# RF_VCO.net
KiCad netlist of a schematic drawn in Altium Designer
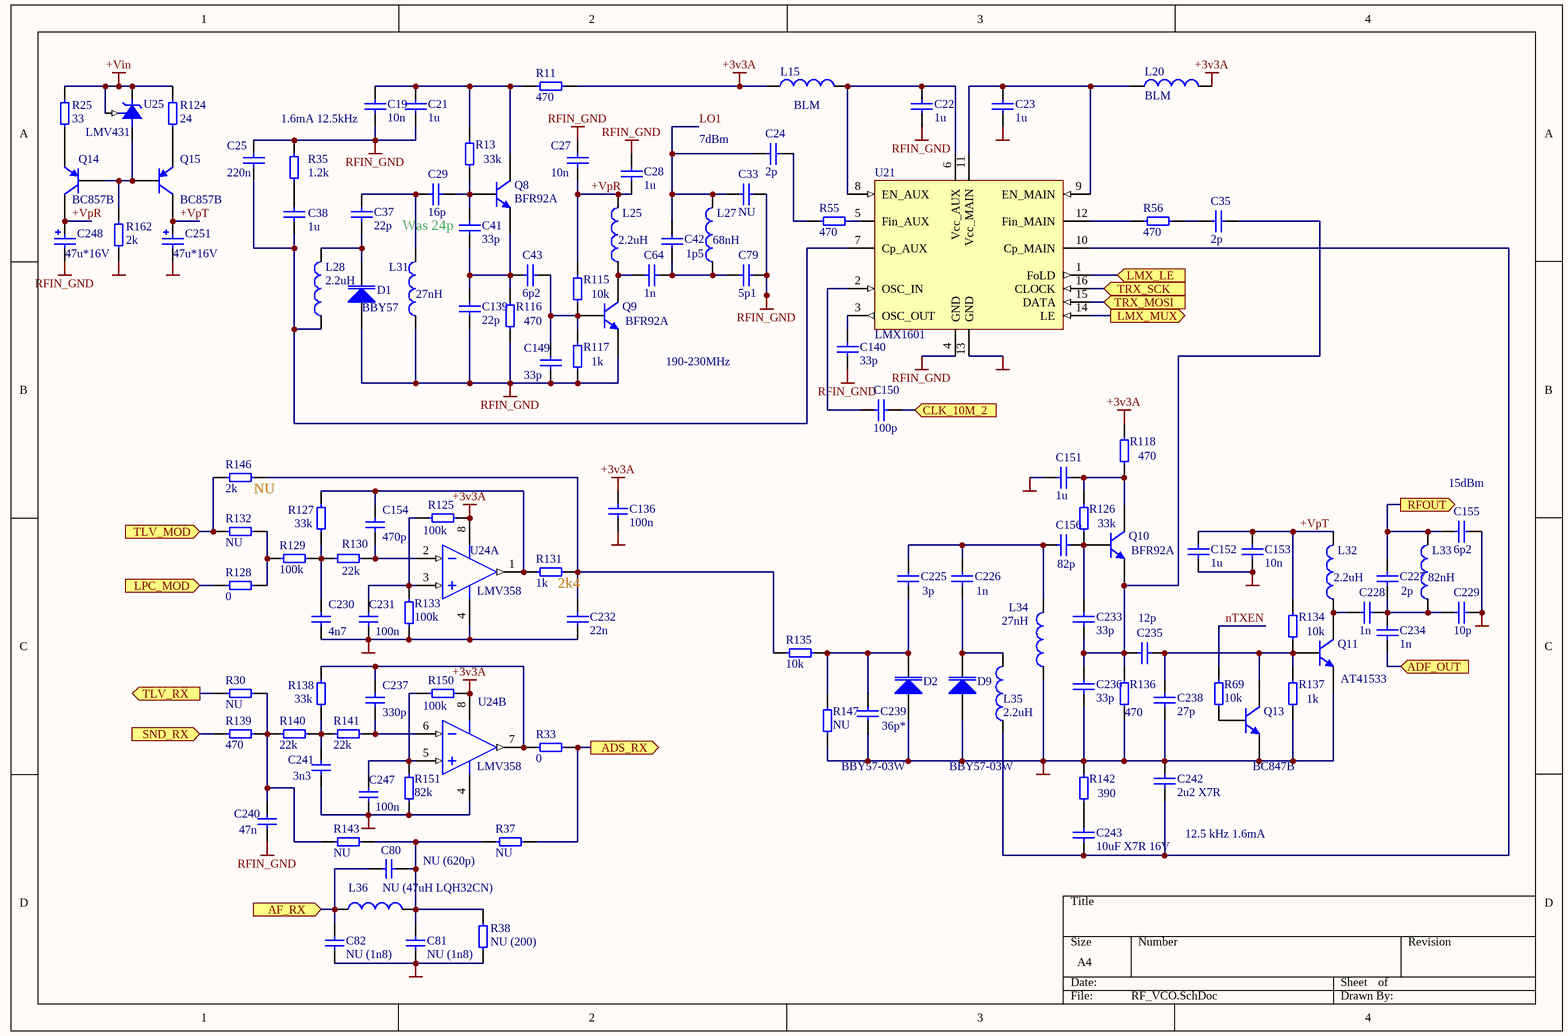
[diagram p0: RF_VCO.SchDoc]

(export (version "E")
  (design (tool "Eeschema 10.0.6"))
  (components
    (comp (ref "C19")
      (value "10n")
      (footprint "CAPC1608L")
      (description "Capacitor")
      (fields (field (name "PUBLISHER") "Altium Limited"))
      (libsource (lib "MyLibrary") (part "Cap"))
    )
    (comp (ref "C21")
      (value "1u")
      (footprint "CAPC2012L")
      (description "Capacitor")
      (fields (field (name "PUBLISHER") "Altium Limited"))
      (libsource (lib "MyLibrary") (part "Cap"))
    )
    (comp (ref "C22")
      (value "1u")
      (footprint "CAPC2012L")
      (description "Capacitor")
      (fields (field (name "PUBLISHER") "Altium Limited"))
      (libsource (lib "Sch components") (part "Cap"))
    )
    (comp (ref "C23")
      (value "1u")
      (footprint "CAPC2012L")
      (description "Capacitor")
      (fields (field (name "PUBLISHER") "Altium Limited"))
      (libsource (lib "Sch components") (part "Cap"))
    )
    (comp (ref "C24")
      (value "2p")
      (footprint "CAPC1608L")
      (description "Capacitor")
      (fields (field (name "PUBLISHER") "Altium Limited"))
      (libsource (lib "Sch components") (part "Cap"))
    )
    (comp (ref "C25")
      (value "220n")
      (footprint "CAPC1608L")
      (description "Capacitor")
      (fields (field (name "PUBLISHER") "Altium Limited"))
      (libsource (lib "MyLibrary") (part "Cap"))
    )
    (comp (ref "C27")
      (value "10n")
      (footprint "CAPC1608L")
      (description "Capacitor")
      (fields (field (name "PUBLISHER") "Altium Limited"))
      (libsource (lib "MyLibrary") (part "Cap"))
    )
    (comp (ref "C28")
      (value "1u")
      (footprint "CAPC2012L")
      (description "Capacitor")
      (fields (field (name "PUBLISHER") "Altium Limited"))
      (libsource (lib "MyLibrary") (part "Cap"))
    )
    (comp (ref "C29")
      (value "16p")
      (footprint "CAPC1608L")
      (description "Capacitor")
      (fields (field (name "PUBLISHER") "Altium Limited"))
      (libsource (lib "MyLibrary") (part "Cap"))
    )
    (comp (ref "C33")
      (value "NU")
      (footprint "CAPC1608L")
      (description "Capacitor")
      (fields (field (name "PUBLISHER") "Altium Limited"))
      (libsource (lib "MyLibrary") (part "Cap"))
    )
    (comp (ref "C35")
      (value "2p")
      (footprint "CAPC1608L")
      (description "Capacitor")
      (fields (field (name "PUBLISHER") "Altium Limited"))
      (libsource (lib "MyLibrary") (part "Cap"))
    )
    (comp (ref "C37")
      (value "22p")
      (footprint "CAPC1608L")
      (description "Capacitor")
      (fields (field (name "PUBLISHER") "Altium Limited"))
      (libsource (lib "MyLibrary") (part "Cap"))
    )
    (comp (ref "C38")
      (value "1u")
      (footprint "CAPC2012L")
      (description "Capacitor")
      (fields (field (name "PUBLISHER") "Altium Limited"))
      (libsource (lib "MyLibrary") (part "Cap"))
    )
    (comp (ref "C41")
      (value "33p")
      (footprint "CAPC1608L")
      (description "Capacitor")
      (fields (field (name "PUBLISHER") "Altium Limited"))
      (libsource (lib "MyLibrary") (part "Cap"))
    )
    (comp (ref "C42")
      (value "1p5")
      (footprint "CAPC1608L")
      (description "Capacitor")
      (fields (field (name "PUBLISHER") "Altium Limited"))
      (libsource (lib "MyLibrary") (part "Cap"))
    )
    (comp (ref "C43")
      (value "6p2")
      (footprint "CAPC1608L")
      (description "Capacitor")
      (fields (field (name "PUBLISHER") "Altium Limited"))
      (libsource (lib "MyLibrary") (part "Cap"))
    )
    (comp (ref "C64")
      (value "1n")
      (footprint "CAPC1608L")
      (description "Capacitor")
      (fields (field (name "PUBLISHER") "Altium Limited"))
      (libsource (lib "MyLibrary") (part "Cap"))
    )
    (comp (ref "C79")
      (value "5p1")
      (footprint "CAPC1608L")
      (description "Capacitor")
      (fields (field (name "PUBLISHER") "Altium Limited"))
      (libsource (lib "MyLibrary") (part "Cap"))
    )
    (comp (ref "C80")
      (value "NU (620p)")
      (footprint "CAPC1608L")
      (description "Capacitor")
      (fields (field (name "PUBLISHER") "Altium Limited"))
      (libsource (lib "") (part "Cap_1"))
    )
    (comp (ref "C81")
      (value "NU (1n8)")
      (footprint "CAPC1608L")
      (description "Capacitor")
      (fields (field (name "PUBLISHER") "Altium Limited"))
      (libsource (lib "") (part "Cap_1"))
    )
    (comp (ref "C82")
      (value "NU (1n8)")
      (footprint "CAPC1608L")
      (description "Capacitor")
      (fields (field (name "PUBLISHER") "Altium Limited"))
      (libsource (lib "") (part "Cap_1"))
    )
    (comp (ref "C136")
      (value "100n")
      (footprint "CAPC1608L")
      (description "Capacitor")
      (fields (field (name "PUBLISHER") "Altium Limited"))
      (libsource (lib "") (part "Cap_1"))
    )
    (comp (ref "C139")
      (value "22p")
      (footprint "CAPC1608L")
      (description "Capacitor")
      (fields (field (name "PUBLISHER") "Altium Limited"))
      (libsource (lib "MyLibrary") (part "Cap"))
    )
    (comp (ref "C140")
      (value "33p")
      (footprint "CAPC1608L")
      (description "Capacitor")
      (fields (field (name "PUBLISHER") "Altium Limited"))
      (libsource (lib "MyLibrary") (part "Cap"))
    )
    (comp (ref "C149")
      (value "33p")
      (footprint "CAPC1608L")
      (description "Capacitor")
      (fields (field (name "PUBLISHER") "Altium Limited"))
      (libsource (lib "MyLibrary") (part "Cap"))
    )
    (comp (ref "C150")
      (value "100p")
      (footprint "CAPC1608L")
      (description "Capacitor")
      (fields (field (name "PUBLISHER") "Altium Limited"))
      (libsource (lib "MyLibrary") (part "Cap"))
    )
    (comp (ref "C151")
      (value "1u")
      (footprint "CAPC2012L")
      (description "Capacitor")
      (fields (field (name "PUBLISHER") "Altium Limited"))
      (libsource (lib "MyLibrary") (part "Cap"))
    )
    (comp (ref "C152")
      (value "1u")
      (footprint "CAPC2012L")
      (description "Capacitor")
      (fields (field (name "PUBLISHER") "Altium Limited"))
      (libsource (lib "MyLibrary") (part "Cap"))
    )
    (comp (ref "C153")
      (value "10n")
      (footprint "CAPC1608L")
      (description "Capacitor")
      (fields (field (name "PUBLISHER") "Altium Limited"))
      (libsource (lib "MyLibrary") (part "Cap"))
    )
    (comp (ref "C154")
      (value "470p")
      (footprint "CAPC1608L")
      (description "Capacitor")
      (fields (field (name "PUBLISHER") "Altium Limited"))
      (libsource (lib "") (part "Cap_1"))
    )
    (comp (ref "C155")
      (value "6p2")
      (footprint "CAPC1608L")
      (description "Capacitor")
      (fields (field (name "PUBLISHER") "Altium Limited"))
      (libsource (lib "MyLibrary") (part "Cap"))
    )
    (comp (ref "C156")
      (value "82p")
      (footprint "CAPC1608L")
      (description "Capacitor")
      (fields (field (name "PUBLISHER") "Altium Limited"))
      (libsource (lib "MyLibrary") (part "Cap"))
    )
    (comp (ref "C225")
      (value "3p")
      (footprint "CAPC1608L")
      (description "Capacitor")
      (fields (field (name "PUBLISHER") "Altium Limited"))
      (libsource (lib "MyLibrary") (part "Cap"))
    )
    (comp (ref "C226")
      (value "1n")
      (footprint "CAPC1608L")
      (description "Capacitor")
      (fields (field (name "PUBLISHER") "Altium Limited"))
      (libsource (lib "MyLibrary") (part "Cap"))
    )
    (comp (ref "C227")
      (value "2p")
      (footprint "CAPC1608L")
      (description "Capacitor")
      (fields (field (name "PUBLISHER") "Altium Limited"))
      (libsource (lib "MyLibrary") (part "Cap"))
    )
    (comp (ref "C228")
      (value "1n")
      (footprint "CAPC1608L")
      (description "Capacitor")
      (fields (field (name "PUBLISHER") "Altium Limited"))
      (libsource (lib "MyLibrary") (part "Cap"))
    )
    (comp (ref "C229")
      (value "10p")
      (footprint "CAPC1608L")
      (description "Capacitor")
      (fields (field (name "PUBLISHER") "Altium Limited"))
      (libsource (lib "MyLibrary") (part "Cap"))
    )
    (comp (ref "C230")
      (value "4n7")
      (footprint "CAPC1608L")
      (description "Capacitor")
      (fields (field (name "PUBLISHER") "Altium Limited"))
      (libsource (lib "") (part "Cap_1"))
    )
    (comp (ref "C231")
      (value "100n")
      (footprint "CAPC1608L")
      (description "Capacitor")
      (fields (field (name "PUBLISHER") "Altium Limited"))
      (libsource (lib "") (part "Cap_1"))
    )
    (comp (ref "C232")
      (value "22n")
      (footprint "CAPC1608L")
      (description "Capacitor")
      (fields (field (name "PUBLISHER") "Altium Limited"))
      (libsource (lib "Sch components") (part "Cap"))
    )
    (comp (ref "C233")
      (value "33p")
      (footprint "CAPC1608L")
      (description "Capacitor")
      (fields (field (name "PUBLISHER") "Altium Limited"))
      (libsource (lib "MyLibrary") (part "Cap"))
    )
    (comp (ref "C234")
      (value "1n")
      (footprint "CAPC1608L")
      (description "Capacitor")
      (fields (field (name "PUBLISHER") "Altium Limited"))
      (libsource (lib "MyLibrary") (part "Cap"))
    )
    (comp (ref "C235")
      (value "12p")
      (footprint "CAPC1608L")
      (description "Capacitor")
      (fields (field (name "PUBLISHER") "Altium Limited"))
      (libsource (lib "MyLibrary") (part "Cap"))
    )
    (comp (ref "C236")
      (value "33p")
      (footprint "CAPC1608L")
      (description "Capacitor")
      (fields (field (name "PUBLISHER") "Altium Limited"))
      (libsource (lib "MyLibrary") (part "Cap"))
    )
    (comp (ref "C237")
      (value "330p")
      (footprint "CAPC1608L")
      (description "Capacitor")
      (fields (field (name "PUBLISHER") "Altium Limited"))
      (libsource (lib "") (part "Cap_1"))
    )
    (comp (ref "C238")
      (value "27p")
      (footprint "CAPC1608L")
      (description "Capacitor")
      (fields (field (name "PUBLISHER") "Altium Limited"))
      (libsource (lib "MyLibrary") (part "Cap"))
    )
    (comp (ref "C239")
      (value "36p*")
      (footprint "CAPC1608L")
      (description "Capacitor")
      (fields (field (name "PUBLISHER") "Altium Limited"))
      (libsource (lib "MyLibrary") (part "Cap"))
    )
    (comp (ref "C240")
      (value "47n")
      (footprint "CAPC1608L")
      (description "Capacitor")
      (fields (field (name "PUBLISHER") "Altium Limited"))
      (libsource (lib "") (part "Cap_1"))
    )
    (comp (ref "C241")
      (value "3n3")
      (footprint "CAPC1608L")
      (description "Capacitor")
      (fields (field (name "PUBLISHER") "Altium Limited"))
      (libsource (lib "") (part "Cap_1"))
    )
    (comp (ref "C242")
      (value "2u2 X7R")
      (footprint "CAPC2012L")
      (description "Capacitor")
      (fields (field (name "PUBLISHER") "Altium Limited"))
      (libsource (lib "MyLibrary") (part "Cap"))
    )
    (comp (ref "C243")
      (value "10uF X7R 16V")
      (footprint "CAPC3216M")
      (description "Capacitor")
      (fields (field (name "PUBLISHER") "Altium Limited"))
      (libsource (lib "Sch components") (part "Cap"))
    )
    (comp (ref "C247")
      (value "100n")
      (footprint "CAPC1608L")
      (description "Capacitor")
      (fields (field (name "PUBLISHER") "Altium Limited"))
      (libsource (lib "") (part "Cap_1"))
    )
    (comp (ref "C248")
      (value "47u*16V")
      (footprint "Case_C")
      (description "Polarized Capacitor (Surface Mount)")
      (fields (field (name "PUBLISHER") "Altium Limited"))
      (libsource (lib "Sch components") (part "Cap Pol"))
    )
    (comp (ref "C251")
      (value "47u*16V")
      (footprint "Case_C")
      (description "Polarized Capacitor (Surface Mount)")
      (fields (field (name "PUBLISHER") "Altium Limited"))
      (libsource (lib "Sch components") (part "Cap Pol"))
    )
    (comp (ref "D1")
      (value "BBY57")
      (footprint "SOD-323")
      (description "Silicon High Q Hyperabrupt Tuning Diode")
      (fields (field (name "PUBLISHER") "Altium Limited"))
      (libsource (lib "Infineon Discrete Diode") (part "BBY57-03W"))
    )
    (comp (ref "D2")
      (value "BBY57-03W")
      (footprint "SOD-323")
      (description "Silicon High Q Hyperabrupt Tuning Diode")
      (fields (field (name "PUBLISHER") "Altium Limited"))
      (libsource (lib "Infineon Discrete Diode") (part "BBY57-03W"))
    )
    (comp (ref "D9")
      (value "BBY57-03W")
      (footprint "SOD-323")
      (description "Silicon High Q Hyperabrupt Tuning Diode")
      (fields (field (name "PUBLISHER") "Altium Limited"))
      (libsource (lib "Infineon Discrete Diode") (part "BBY57-03W"))
    )
    (comp (ref "L15")
      (value "BLM")
      (footprint "CAPC2012N")
      (description "Ferrite Bead")
      (fields (field (name "PUBLISHER") "Altium Limited"))
      (libsource (lib "Sch components") (part "Ferrite Bead"))
    )
    (comp (ref "L20")
      (value "BLM")
      (footprint "CAPC2012N")
      (description "Ferrite Bead")
      (fields (field (name "PUBLISHER") "Altium Limited"))
      (libsource (lib "") (part "Ferrite Bead_1"))
    )
    (comp (ref "L25") (value "2.2uH") (footprint "INDC2012L") (libsource (lib "MyLibrary") (part "INDUCTOR")))
    (comp (ref "L27") (value "68nH") (footprint "INDC2012L") (libsource (lib "MyLibrary") (part "INDUCTOR")))
    (comp (ref "L28") (value "2.2uH") (footprint "INDC2012L") (libsource (lib "MyLibrary") (part "INDUCTOR")))
    (comp (ref "L31") (value "27nH") (footprint "INDC2012L") (libsource (lib "MyLibrary") (part "INDUCTOR")))
    (comp (ref "L32") (value "2.2uH") (footprint "INDC2012L") (libsource (lib "MyLibrary") (part "INDUCTOR")))
    (comp (ref "L33") (value "82nH") (footprint "INDC2012L") (libsource (lib "MyLibrary") (part "INDUCTOR")))
    (comp (ref "L34") (value "27nH") (footprint "INDC2012L") (libsource (lib "MyLibrary") (part "INDUCTOR")))
    (comp (ref "L35") (value "2.2uH") (footprint "INDC2012L") (libsource (lib "MyLibrary") (part "INDUCTOR")))
    (comp (ref "L36")
      (value "NU (47uH LQH32CN)")
      (footprint "CAPC3225N")
      (libsource (lib "MyLibrary") (part "INDUCTOR"))
    )
    (comp (ref "Q8")
      (value "BFR92A")
      (footprint "SOT-23")
      (description "NPN 5 GHz Wideband Transistor")
      (fields (field (name "PUBLISHER") "Altium Limited"))
      (libsource (lib "Philips Discrete BJT - RF Transistor") (part "BFR92A"))
    )
    (comp (ref "Q9")
      (value "BFR92A")
      (footprint "SOT-23")
      (description "NPN 5 GHz Wideband Transistor")
      (fields (field (name "PUBLISHER") "Altium Limited"))
      (libsource (lib "Philips Discrete BJT - RF Transistor") (part "BFR92A"))
    )
    (comp (ref "Q10")
      (value "BFR92A")
      (footprint "SOT-23")
      (description "NPN 5 GHz Wideband Transistor")
      (fields (field (name "PUBLISHER") "Altium Limited"))
      (libsource (lib "Philips Discrete BJT - RF Transistor") (part "BFR92A"))
    )
    (comp (ref "Q11")
      (value "AT41533")
      (footprint "SOT-23")
      (description "NPN 5 GHz Wideband Transistor")
      (fields (field (name "PUBLISHER") "Altium Limited"))
      (libsource (lib "Philips Discrete BJT - RF Transistor") (part "BFR92A"))
    )
    (comp (ref "Q13")
      (value "BC847B")
      (footprint "SOT23_N")
      (description "NPN General-purpose Transistor")
      (fields (field (name "PUBLISHER") "Altium Limited"))
      (libsource (lib "Philips Discrete BJT - Low Power") (part "BC847B"))
    )
    (comp (ref "Q14")
      (value "BC857B")
      (footprint "SOT23_N")
      (description "PNP General-purpose Transistor")
      (fields (field (name "PUBLISHER") "Altium Limited"))
      (libsource (lib "Philips Discrete BJT - Low Power") (part "BC857B"))
    )
    (comp (ref "Q15")
      (value "BC857B")
      (footprint "SOT23_N")
      (description "PNP General-purpose Transistor")
      (fields (field (name "PUBLISHER") "Altium Limited"))
      (libsource (lib "Philips Discrete BJT - Low Power") (part "BC857B"))
    )
    (comp (ref "R11")
      (value "470")
      (footprint "RESC1608L")
      (description "Resistor")
      (fields (field (name "PUBLISHER") "Altium Limited"))
      (libsource (lib "Sch components") (part "Res"))
    )
    (comp (ref "R13")
      (value "33k")
      (footprint "RESC1608L")
      (description "Resistor")
      (fields (field (name "PUBLISHER") "Altium Limited"))
      (libsource (lib "Sch components") (part "Res"))
    )
    (comp (ref "R25")
      (value "33")
      (footprint "RESC1608L")
      (description "Resistor")
      (fields (field (name "PUBLISHER") "Altium Limited"))
      (libsource (lib "Sch components") (part "Res"))
    )
    (comp (ref "R30")
      (value "NU")
      (footprint "RESC1608L")
      (description "Resistor")
      (fields (field (name "PUBLISHER") "Altium Limited"))
      (libsource (lib "Sch components") (part "Res"))
    )
    (comp (ref "R33")
      (value "0")
      (footprint "RESC1608L")
      (description "Resistor")
      (fields (field (name "PUBLISHER") "Altium Limited"))
      (libsource (lib "Sch components") (part "Res"))
    )
    (comp (ref "R35")
      (value "1.2k")
      (footprint "RESC1608L")
      (description "Resistor")
      (fields (field (name "PUBLISHER") "Altium Limited"))
      (libsource (lib "Sch components") (part "Res"))
    )
    (comp (ref "R37")
      (value "NU")
      (footprint "RESC1608L")
      (description "Resistor")
      (fields (field (name "PUBLISHER") "Altium Limited"))
      (libsource (lib "") (part "Res_1"))
    )
    (comp (ref "R38")
      (value "NU (200)")
      (footprint "RESC1608L")
      (description "Resistor")
      (fields (field (name "PUBLISHER") "Altium Limited"))
      (libsource (lib "Sch components") (part "Res"))
    )
    (comp (ref "R55")
      (value "470")
      (footprint "RESC1608L")
      (description "Resistor")
      (fields (field (name "PUBLISHER") "Altium Limited"))
      (libsource (lib "Sch components") (part "Res"))
    )
    (comp (ref "R56")
      (value "470")
      (footprint "RESC1608L")
      (description "Resistor")
      (fields (field (name "PUBLISHER") "Altium Limited"))
      (libsource (lib "Sch components") (part "Res"))
    )
    (comp (ref "R69")
      (value "10k")
      (footprint "RESC1608L")
      (description "Resistor")
      (fields (field (name "PUBLISHER") "Altium Limited"))
      (libsource (lib "Sch components") (part "Res"))
    )
    (comp (ref "R115")
      (value "10k")
      (footprint "RESC1608L")
      (description "Resistor")
      (fields (field (name "PUBLISHER") "Altium Limited"))
      (libsource (lib "Sch components") (part "Res"))
    )
    (comp (ref "R116")
      (value "470")
      (footprint "RESC1608L")
      (description "Resistor")
      (fields (field (name "PUBLISHER") "Altium Limited"))
      (libsource (lib "Sch components") (part "Res"))
    )
    (comp (ref "R117")
      (value "1k")
      (footprint "RESC1608L")
      (description "Resistor")
      (fields (field (name "PUBLISHER") "Altium Limited"))
      (libsource (lib "Sch components") (part "Res"))
    )
    (comp (ref "R118")
      (value "470")
      (footprint "RESC1608L")
      (description "Resistor")
      (fields (field (name "PUBLISHER") "Altium Limited"))
      (libsource (lib "Sch components") (part "Res"))
    )
    (comp (ref "R124")
      (value "24")
      (footprint "RESC1608L")
      (description "Resistor")
      (fields (field (name "PUBLISHER") "Altium Limited"))
      (libsource (lib "Sch components") (part "Res"))
    )
    (comp (ref "R125")
      (value "100k")
      (footprint "RESC1608L")
      (description "Resistor")
      (fields (field (name "PUBLISHER") "Altium Limited"))
      (libsource (lib "Sch components") (part "Res"))
    )
    (comp (ref "R126")
      (value "33k")
      (footprint "RESC1608L")
      (description "Resistor")
      (fields (field (name "PUBLISHER") "Altium Limited"))
      (libsource (lib "Sch components") (part "Res"))
    )
    (comp (ref "R127")
      (value "33k")
      (footprint "RESC1608L")
      (description "Resistor")
      (fields (field (name "PUBLISHER") "Altium Limited"))
      (libsource (lib "Sch components") (part "Res"))
    )
    (comp (ref "R128")
      (value "0")
      (footprint "RESC1608L")
      (description "Resistor")
      (fields (field (name "PUBLISHER") "Altium Limited"))
      (libsource (lib "Sch components") (part "Res"))
    )
    (comp (ref "R129")
      (value "100k")
      (footprint "RESC1608L")
      (description "Resistor")
      (fields (field (name "PUBLISHER") "Altium Limited"))
      (libsource (lib "Sch components") (part "Res"))
    )
    (comp (ref "R130")
      (value "22k")
      (footprint "RESC1608L")
      (description "Resistor")
      (fields (field (name "PUBLISHER") "Altium Limited"))
      (libsource (lib "Sch components") (part "Res"))
    )
    (comp (ref "R131")
      (value "1k")
      (footprint "RESC1608L")
      (description "Resistor")
      (fields (field (name "PUBLISHER") "Altium Limited"))
      (libsource (lib "Sch components") (part "Res"))
    )
    (comp (ref "R132")
      (value "NU")
      (footprint "RESC1608L")
      (description "Resistor")
      (fields (field (name "PUBLISHER") "Altium Limited"))
      (libsource (lib "Sch components") (part "Res"))
    )
    (comp (ref "R133")
      (value "100k")
      (footprint "RESC1608L")
      (description "Resistor")
      (fields (field (name "PUBLISHER") "Altium Limited"))
      (libsource (lib "Sch components") (part "Res"))
    )
    (comp (ref "R134")
      (value "10k")
      (footprint "RESC1608L")
      (description "Resistor")
      (fields (field (name "PUBLISHER") "Altium Limited"))
      (libsource (lib "Sch components") (part "Res"))
    )
    (comp (ref "R135")
      (value "10k")
      (footprint "RESC1608L")
      (description "Resistor")
      (fields (field (name "PUBLISHER") "Altium Limited"))
      (libsource (lib "Sch components") (part "Res"))
    )
    (comp (ref "R136")
      (value "470")
      (footprint "RESC1608L")
      (description "Resistor")
      (fields (field (name "PUBLISHER") "Altium Limited"))
      (libsource (lib "Sch components") (part "Res"))
    )
    (comp (ref "R137")
      (value "1k")
      (footprint "RESC1608L")
      (description "Resistor")
      (fields (field (name "PUBLISHER") "Altium Limited"))
      (libsource (lib "Sch components") (part "Res"))
    )
    (comp (ref "R138")
      (value "33k")
      (footprint "RESC1608L")
      (description "Resistor")
      (fields (field (name "PUBLISHER") "Altium Limited"))
      (libsource (lib "Sch components") (part "Res"))
    )
    (comp (ref "R139")
      (value "470")
      (footprint "RESC1608L")
      (description "Resistor")
      (fields (field (name "PUBLISHER") "Altium Limited"))
      (libsource (lib "Sch components") (part "Res"))
    )
    (comp (ref "R140")
      (value "22k")
      (footprint "RESC1608L")
      (description "Resistor")
      (fields (field (name "PUBLISHER") "Altium Limited"))
      (libsource (lib "Sch components") (part "Res"))
    )
    (comp (ref "R141")
      (value "22k")
      (footprint "RESC1608L")
      (description "Resistor")
      (fields (field (name "PUBLISHER") "Altium Limited"))
      (libsource (lib "Sch components") (part "Res"))
    )
    (comp (ref "R142")
      (value "390")
      (footprint "RESC1608L")
      (description "Resistor")
      (fields (field (name "PUBLISHER") "Altium Limited"))
      (libsource (lib "Sch components") (part "Res"))
    )
    (comp (ref "R143")
      (value "NU")
      (footprint "RESC1608L")
      (description "Resistor")
      (fields (field (name "PUBLISHER") "Altium Limited"))
      (libsource (lib "") (part "Res_1"))
    )
    (comp (ref "R146")
      (value "2k")
      (footprint "RESC1608L")
      (description "Resistor")
      (fields (field (name "PUBLISHER") "Altium Limited"))
      (libsource (lib "Sch components") (part "Res"))
    )
    (comp (ref "R147")
      (value "NU")
      (footprint "RESC1608L")
      (description "Resistor")
      (fields (field (name "PUBLISHER") "Altium Limited"))
      (libsource (lib "Sch components") (part "Res"))
    )
    (comp (ref "R150")
      (value "100k")
      (footprint "RESC1608L")
      (description "Resistor")
      (fields (field (name "PUBLISHER") "Altium Limited"))
      (libsource (lib "Sch components") (part "Res"))
    )
    (comp (ref "R151")
      (value "82k")
      (footprint "RESC1608L")
      (description "Resistor")
      (fields (field (name "PUBLISHER") "Altium Limited"))
      (libsource (lib "Sch components") (part "Res"))
    )
    (comp (ref "R162")
      (value "2k")
      (footprint "RESC1608L")
      (description "Resistor")
      (fields (field (name "PUBLISHER") "Altium Limited"))
      (libsource (lib "Sch components") (part "Res"))
    )
    (comp (ref "U21")
      (value "LMX1601")
      (footprint "TSSOP65P640X120-16N")
      (description "Synthesizer")
      (libsource (lib "Sch components") (part "LMX1601"))
    )
    (comp (ref "U24")
      (value "LMV358")
      (footprint "SOIC-150-8")
      (description "General Purpose, Low Voltage, Rail-to-Rail Output Operational Amplifiers")
      (fields
        (field (name "PARTNUMBER") "LMV358M")
        (field (name "MANUFACTURER") "National Semiconductor")
        (field (name "PUBLISHER") "Altium Limited")
      )
      (libsource (lib "*") (part "LMV358M"))
    )
    (comp (ref "U25")
      (value "LMV431")
      (footprint "MF03A_N")
      (description "Low-Voltage (1.24V) Adjustable Precision Shunt Regulator")
      (fields
        (field (name "PARTNUMBER") "LMV431AIMF")
        (field (name "MANUFACTURER") "National Semiconductor")
        (field (name "PUBLISHER") "Altium Limited")
      )
      (libsource (lib "NSC MiscPower") (part "LMV431AIMF"))
    )
  )
  (nets
    (net (code "1") (name "+3v3A") (class "Default")
      (node (ref "C136") (pin "1") (pinfunction "1_1") (pintype "passive"))
      (node (ref "L15") (pin "2") (pinfunction "2_2") (pintype "passive"))
      (node (ref "L20") (pin "2") (pinfunction "2_2") (pintype "passive"))
      (node (ref "R11") (pin "2") (pinfunction "2_2") (pintype "passive"))
      (node (ref "R118") (pin "1") (pinfunction "1_1") (pintype "passive"))
      (node (ref "R125") (pin "2") (pinfunction "2_2") (pintype "passive"))
      (node (ref "R150") (pin "2") (pinfunction "2_2") (pintype "passive"))
      (node (ref "U24") (pin "8") (pinfunction "V+_8") (pintype "power_in"))
    )
    (net (code "2") (name "+Vin") (class "Default")
      (node (ref "R124") (pin "2") (pinfunction "2_2") (pintype "passive"))
      (node (ref "R25") (pin "2") (pinfunction "2_2") (pintype "passive"))
      (node (ref "U25") (pin "1") (pinfunction "REF_1") (pintype "input"))
      (node (ref "U25") (pin "2") (pinfunction "K_2") (pintype "passive"))
    )
    (net (code "3") (name "/+VpR") (class "Default")
      (node (ref "C248") (pin "1") (pinfunction "1_1") (pintype "passive"))
      (node (ref "C27") (pin "2") (pinfunction "2_2") (pintype "passive"))
      (node (ref "C28") (pin "2") (pinfunction "2_2") (pintype "passive"))
      (node (ref "L25") (pin "2") (pinfunction "2_2") (pintype "passive"))
      (node (ref "Q14") (pin "3") (pinfunction "C_3") (pintype "passive"))
      (node (ref "R115") (pin "1") (pinfunction "1_1") (pintype "passive"))
    )
    (net (code "4") (name "/+VpT") (class "Default")
      (node (ref "C152") (pin "2") (pinfunction "2_2") (pintype "passive"))
      (node (ref "C153") (pin "2") (pinfunction "2_2") (pintype "passive"))
      (node (ref "C251") (pin "1") (pinfunction "1_1") (pintype "passive"))
      (node (ref "L32") (pin "2") (pinfunction "2_2") (pintype "passive"))
      (node (ref "Q15") (pin "3") (pinfunction "C_3") (pintype "passive"))
      (node (ref "R134") (pin "1") (pinfunction "1_1") (pintype "passive"))
    )
    (net (code "5") (name "/ADF_OUT") (class "Default")
      (node (ref "C234") (pin "2") (pinfunction "2_2") (pintype "passive"))
    )
    (net (code "6") (name "/ADS_RX") (class "Default")
      (node (ref "R33") (pin "2") (pinfunction "2_2") (pintype "passive"))
      (node (ref "R37") (pin "1") (pinfunction "1_1") (pintype "passive"))
    )
    (net (code "7") (name "/AF_RX") (class "Default")
      (node (ref "C80") (pin "2") (pinfunction "2_2") (pintype "passive"))
      (node (ref "C82") (pin "2") (pinfunction "2_2") (pintype "passive"))
      (node (ref "L36") (pin "1") (pinfunction "1_1") (pintype "passive"))
    )
    (net (code "8") (name "/CLK_10M_2") (class "Default")
      (node (ref "C150") (pin "2") (pinfunction "2_2") (pintype "passive"))
    )
    (net (code "9") (name "/LMX_LE") (class "Default")
      (node (ref "U21") (pin "1") (pinfunction "FoLD_1") (pintype "output"))
    )
    (net (code "10") (name "/LMX_MUX") (class "Default")
      (node (ref "U21") (pin "14") (pinfunction "LE_14") (pintype "input"))
    )
    (net (code "11") (name "/LO1") (class "Default")
      (node (ref "C24") (pin "1") (pinfunction "1_1") (pintype "passive"))
      (node (ref "C33") (pin "1") (pinfunction "1_1") (pintype "passive"))
      (node (ref "C42") (pin "2") (pinfunction "2_2") (pintype "passive"))
      (node (ref "L27") (pin "2") (pinfunction "2_2") (pintype "passive"))
    )
    (net (code "12") (name "/LPC_MOD") (class "Default")
      (node (ref "R128") (pin "1") (pinfunction "1_1") (pintype "passive"))
    )
    (net (code "13") (name "/RFOUT") (class "Default")
      (node (ref "C155") (pin "1") (pinfunction "1_1") (pintype "passive"))
      (node (ref "C227") (pin "2") (pinfunction "2_2") (pintype "passive"))
      (node (ref "L33") (pin "2") (pinfunction "2_2") (pintype "passive"))
    )
    (net (code "14") (name "/SND_RX") (class "Default")
      (node (ref "R139") (pin "2") (pinfunction "2_2") (pintype "passive"))
    )
    (net (code "15") (name "/TLV_MOD") (class "Default")
      (node (ref "R132") (pin "1") (pinfunction "1_1") (pintype "passive"))
      (node (ref "R146") (pin "1") (pinfunction "1_1") (pintype "passive"))
    )
    (net (code "16") (name "/TLV_RX") (class "Default")
      (node (ref "R30") (pin "2") (pinfunction "2_2") (pintype "passive"))
    )
    (net (code "17") (name "/TRX_MOSI") (class "Default")
      (node (ref "U21") (pin "15") (pinfunction "DATA_15") (pintype "input"))
    )
    (net (code "18") (name "/TRX_SCK") (class "Default")
      (node (ref "U21") (pin "16") (pinfunction "CLOCK_16") (pintype "input"))
    )
    (net (code "19") (name "/nTXEN") (class "Default")
      (node (ref "R69") (pin "1") (pinfunction "1_1") (pintype "passive"))
    )
    (net (code "20") (name "GND") (class "Default")
      (node (ref "C136") (pin "2") (pinfunction "2_2") (pintype "passive"))
      (node (ref "C151") (pin "2") (pinfunction "2_2") (pintype "passive"))
      (node (ref "C152") (pin "1") (pinfunction "1_1") (pintype "passive"))
      (node (ref "C153") (pin "1") (pinfunction "1_1") (pintype "passive"))
      (node (ref "C155") (pin "2") (pinfunction "2_2") (pintype "passive"))
      (node (ref "C229") (pin "2") (pinfunction "2_2") (pintype "passive"))
      (node (ref "C23") (pin "1") (pinfunction "1_1") (pintype "passive"))
      (node (ref "C230") (pin "2") (pinfunction "2_2") (pintype "passive"))
      (node (ref "C231") (pin "2") (pinfunction "2_2") (pintype "passive"))
      (node (ref "C232") (pin "2") (pinfunction "2_2") (pintype "passive"))
      (node (ref "C236") (pin "2") (pinfunction "2_2") (pintype "passive"))
      (node (ref "C238") (pin "2") (pinfunction "2_2") (pintype "passive"))
      (node (ref "C239") (pin "1") (pinfunction "1_1") (pintype "passive"))
      (node (ref "C241") (pin "2") (pinfunction "2_2") (pintype "passive"))
      (node (ref "C242") (pin "1") (pinfunction "1_1") (pintype "passive"))
      (node (ref "C247") (pin "2") (pinfunction "2_2") (pintype "passive"))
      (node (ref "C251") (pin "2") (pinfunction "2_2") (pintype "passive"))
      (node (ref "C81") (pin "1") (pinfunction "1_1") (pintype "passive"))
      (node (ref "C82") (pin "1") (pinfunction "1_1") (pintype "passive"))
      (node (ref "D2") (pin "2") (pinfunction "A_2") (pintype "passive"))
      (node (ref "D9") (pin "2") (pinfunction "A_2") (pintype "passive"))
      (node (ref "L34") (pin "1") (pinfunction "1_1") (pintype "passive"))
      (node (ref "Q11") (pin "2") (pinfunction "E_2") (pintype "passive"))
      (node (ref "Q13") (pin "2") (pinfunction "E_2") (pintype "passive"))
      (node (ref "R133") (pin "2") (pinfunction "2_2") (pintype "passive"))
      (node (ref "R136") (pin "2") (pinfunction "2_2") (pintype "passive"))
      (node (ref "R137") (pin "2") (pinfunction "2_2") (pintype "passive"))
      (node (ref "R142") (pin "1") (pinfunction "1_1") (pintype "passive"))
      (node (ref "R147") (pin "1") (pinfunction "1_1") (pintype "passive"))
      (node (ref "R151") (pin "2") (pinfunction "2_2") (pintype "passive"))
      (node (ref "R162") (pin "1") (pinfunction "1_1") (pintype "passive"))
      (node (ref "R38") (pin "2") (pinfunction "2_2") (pintype "passive"))
      (node (ref "U21") (pin "13") (pinfunction "GND_13") (pintype "power_in"))
      (node (ref "U24") (pin "4") (pinfunction "V-_4") (pintype "power_in"))
    )
    (net (code "21") (name "Net-(C24-Pad2)") (class "Default")
      (node (ref "C24") (pin "2") (pinfunction "2_2") (pintype "passive"))
      (node (ref "R55") (pin "1") (pinfunction "1_1") (pintype "passive"))
    )
    (net (code "22") (name "Net-(C29-Pad2)") (class "Default")
      (node (ref "C29") (pin "2") (pinfunction "2_2") (pintype "passive"))
      (node (ref "C37") (pin "2") (pinfunction "2_2") (pintype "passive"))
      (node (ref "L31") (pin "2") (pinfunction "2_2") (pintype "passive"))
    )
    (net (code "23") (name "Net-(C35-Pad1)") (class "Default")
      (node (ref "C35") (pin "1") (pinfunction "1_1") (pintype "passive"))
      (node (ref "R56") (pin "2") (pinfunction "2_2") (pintype "passive"))
    )
    (net (code "24") (name "Net-(C38-Pad1)") (class "Default")
      (node (ref "C38") (pin "1") (pinfunction "1_1") (pintype "passive"))
      (node (ref "R35") (pin "2") (pinfunction "2_2") (pintype "passive"))
    )
    (net (code "25") (name "Net-(C42-Pad1)") (class "Default")
      (node (ref "C42") (pin "1") (pinfunction "1_1") (pintype "passive"))
      (node (ref "C64") (pin "1") (pinfunction "1_1") (pintype "passive"))
      (node (ref "C79") (pin "1") (pinfunction "1_1") (pintype "passive"))
      (node (ref "L27") (pin "1") (pinfunction "1_1") (pintype "passive"))
    )
    (net (code "26") (name "Net-(C80-Pad1)") (class "Default")
      (node (ref "C80") (pin "1") (pinfunction "1_1") (pintype "passive"))
      (node (ref "C81") (pin "2") (pinfunction "2_2") (pintype "passive"))
      (node (ref "L36") (pin "2") (pinfunction "2_2") (pintype "passive"))
      (node (ref "R143") (pin "2") (pinfunction "2_2") (pintype "passive"))
      (node (ref "R37") (pin "2") (pinfunction "2_2") (pintype "passive"))
      (node (ref "R38") (pin "1") (pinfunction "1_1") (pintype "passive"))
    )
    (net (code "27") (name "Net-(C156-Pad2)") (class "Default")
      (node (ref "C156") (pin "2") (pinfunction "2_2") (pintype "passive"))
      (node (ref "C225") (pin "2") (pinfunction "2_2") (pintype "passive"))
      (node (ref "C226") (pin "2") (pinfunction "2_2") (pintype "passive"))
      (node (ref "L34") (pin "2") (pinfunction "2_2") (pintype "passive"))
    )
    (net (code "28") (name "Net-(C227-Pad1)") (class "Default")
      (node (ref "C227") (pin "1") (pinfunction "1_1") (pintype "passive"))
      (node (ref "C228") (pin "1") (pinfunction "1_1") (pintype "passive"))
      (node (ref "C229") (pin "1") (pinfunction "1_1") (pintype "passive"))
      (node (ref "C234") (pin "1") (pinfunction "1_1") (pintype "passive"))
      (node (ref "L33") (pin "1") (pinfunction "1_1") (pintype "passive"))
    )
    (net (code "29") (name "Net-(C230-Pad1)") (class "Default")
      (node (ref "C230") (pin "1") (pinfunction "1_1") (pintype "passive"))
      (node (ref "R127") (pin "2") (pinfunction "2_2") (pintype "passive"))
      (node (ref "R129") (pin "2") (pinfunction "2_2") (pintype "passive"))
      (node (ref "R130") (pin "1") (pinfunction "1_1") (pintype "passive"))
    )
    (net (code "30") (name "Net-(C232-Pad1)") (class "Default")
      (node (ref "C232") (pin "1") (pinfunction "1_1") (pintype "passive"))
      (node (ref "R131") (pin "2") (pinfunction "2_2") (pintype "passive"))
      (node (ref "R135") (pin "1") (pinfunction "1_1") (pintype "passive"))
      (node (ref "R146") (pin "2") (pinfunction "2_2") (pintype "passive"))
    )
    (net (code "31") (name "Net-(C240-Pad1)") (class "Default")
      (node (ref "C240") (pin "1") (pinfunction "1_1") (pintype "passive"))
      (node (ref "R139") (pin "1") (pinfunction "1_1") (pintype "passive"))
      (node (ref "R140") (pin "2") (pinfunction "2_2") (pintype "passive"))
      (node (ref "R143") (pin "1") (pinfunction "1_1") (pintype "passive"))
      (node (ref "R30") (pin "1") (pinfunction "1_1") (pintype "passive"))
    )
    (net (code "32") (name "Net-(C241-Pad1)") (class "Default")
      (node (ref "C241") (pin "1") (pinfunction "1_1") (pintype "passive"))
      (node (ref "R138") (pin "2") (pinfunction "2_2") (pintype "passive"))
      (node (ref "R140") (pin "1") (pinfunction "1_1") (pintype "passive"))
      (node (ref "R141") (pin "2") (pinfunction "2_2") (pintype "passive"))
    )
    (net (code "33") (name "Net-(C243-Pad2)") (class "Default")
      (node (ref "C243") (pin "2") (pinfunction "2_2") (pintype "passive"))
      (node (ref "R142") (pin "2") (pinfunction "2_2") (pintype "passive"))
    )
    (net (code "34") (name "Net-(D1-K)") (class "Default")
      (node (ref "C37") (pin "1") (pinfunction "1_1") (pintype "passive"))
      (node (ref "D1") (pin "1") (pinfunction "K_1") (pintype "passive"))
      (node (ref "L28") (pin "2") (pinfunction "2_2") (pintype "passive"))
    )
    (net (code "35") (name "Net-(D2-K)") (class "Default")
      (node (ref "C225") (pin "1") (pinfunction "1_1") (pintype "passive"))
      (node (ref "C239") (pin "2") (pinfunction "2_2") (pintype "passive"))
      (node (ref "D2") (pin "1") (pinfunction "K_1") (pintype "passive"))
      (node (ref "R135") (pin "2") (pinfunction "2_2") (pintype "passive"))
      (node (ref "R147") (pin "2") (pinfunction "2_2") (pintype "passive"))
    )
    (net (code "36") (name "Net-(D9-K)") (class "Default")
      (node (ref "C226") (pin "1") (pinfunction "1_1") (pintype "passive"))
      (node (ref "D9") (pin "1") (pinfunction "K_1") (pintype "passive"))
      (node (ref "L35") (pin "2") (pinfunction "2_2") (pintype "passive"))
    )
    (net (code "37") (name "Net-(Q8-B)") (class "Default")
      (node (ref "C29") (pin "1") (pinfunction "1_1") (pintype "passive"))
      (node (ref "C41") (pin "1") (pinfunction "1_1") (pintype "passive"))
      (node (ref "Q8") (pin "1") (pinfunction "B_1") (pintype "passive"))
      (node (ref "R13") (pin "2") (pinfunction "2_2") (pintype "passive"))
    )
    (net (code "38") (name "Net-(Q8-C)") (class "Default")
      (node (ref "C19") (pin "2") (pinfunction "2_2") (pintype "passive"))
      (node (ref "C21") (pin "2") (pinfunction "2_2") (pintype "passive"))
      (node (ref "Q8") (pin "3") (pinfunction "C_3") (pintype "passive"))
      (node (ref "R11") (pin "1") (pinfunction "1_1") (pintype "passive"))
      (node (ref "R13") (pin "1") (pinfunction "1_1") (pintype "passive"))
    )
    (net (code "39") (name "Net-(Q8-E)") (class "Default")
      (node (ref "C139") (pin "1") (pinfunction "1_1") (pintype "passive"))
      (node (ref "C41") (pin "2") (pinfunction "2_2") (pintype "passive"))
      (node (ref "C43") (pin "2") (pinfunction "2_2") (pintype "passive"))
      (node (ref "Q8") (pin "2") (pinfunction "E_2") (pintype "passive"))
      (node (ref "R116") (pin "1") (pinfunction "1_1") (pintype "passive"))
    )
    (net (code "40") (name "Net-(Q9-B)") (class "Default")
      (node (ref "C149") (pin "1") (pinfunction "1_1") (pintype "passive"))
      (node (ref "C43") (pin "1") (pinfunction "1_1") (pintype "passive"))
      (node (ref "Q9") (pin "1") (pinfunction "B_1") (pintype "passive"))
      (node (ref "R115") (pin "2") (pinfunction "2_2") (pintype "passive"))
      (node (ref "R117") (pin "1") (pinfunction "1_1") (pintype "passive"))
    )
    (net (code "41") (name "Net-(Q9-C)") (class "Default")
      (node (ref "C64") (pin "2") (pinfunction "2_2") (pintype "passive"))
      (node (ref "L25") (pin "1") (pinfunction "1_1") (pintype "passive"))
      (node (ref "Q9") (pin "3") (pinfunction "C_3") (pintype "passive"))
    )
    (net (code "42") (name "Net-(Q10-B)") (class "Default")
      (node (ref "C156") (pin "1") (pinfunction "1_1") (pintype "passive"))
      (node (ref "C233") (pin "1") (pinfunction "1_1") (pintype "passive"))
      (node (ref "Q10") (pin "1") (pinfunction "B_1") (pintype "passive"))
      (node (ref "R126") (pin "2") (pinfunction "2_2") (pintype "passive"))
    )
    (net (code "43") (name "Net-(Q10-C)") (class "Default")
      (node (ref "C151") (pin "1") (pinfunction "1_1") (pintype "passive"))
      (node (ref "Q10") (pin "3") (pinfunction "C_3") (pintype "passive"))
      (node (ref "R118") (pin "2") (pinfunction "2_2") (pintype "passive"))
      (node (ref "R126") (pin "1") (pinfunction "1_1") (pintype "passive"))
    )
    (net (code "44") (name "Net-(Q10-E)") (class "Default")
      (node (ref "C233") (pin "2") (pinfunction "2_2") (pintype "passive"))
      (node (ref "C235") (pin "1") (pinfunction "1_1") (pintype "passive"))
      (node (ref "C236") (pin "1") (pinfunction "1_1") (pintype "passive"))
      (node (ref "C35") (pin "2") (pinfunction "2_2") (pintype "passive"))
      (node (ref "Q10") (pin "2") (pinfunction "E_2") (pintype "passive"))
      (node (ref "R136") (pin "1") (pinfunction "1_1") (pintype "passive"))
    )
    (net (code "45") (name "Net-(Q11-B)") (class "Default")
      (node (ref "C235") (pin "2") (pinfunction "2_2") (pintype "passive"))
      (node (ref "C238") (pin "1") (pinfunction "1_1") (pintype "passive"))
      (node (ref "Q11") (pin "1") (pinfunction "B_1") (pintype "passive"))
      (node (ref "Q13") (pin "3") (pinfunction "C_3") (pintype "passive"))
      (node (ref "R134") (pin "2") (pinfunction "2_2") (pintype "passive"))
      (node (ref "R137") (pin "1") (pinfunction "1_1") (pintype "passive"))
    )
    (net (code "46") (name "Net-(Q11-C)") (class "Default")
      (node (ref "C228") (pin "2") (pinfunction "2_2") (pintype "passive"))
      (node (ref "L32") (pin "1") (pinfunction "1_1") (pintype "passive"))
      (node (ref "Q11") (pin "3") (pinfunction "C_3") (pintype "passive"))
    )
    (net (code "47") (name "Net-(Q13-B)") (class "Default")
      (node (ref "Q13") (pin "1") (pinfunction "B_1") (pintype "passive"))
      (node (ref "R69") (pin "2") (pinfunction "2_2") (pintype "passive"))
    )
    (net (code "48") (name "Net-(Q14-B)") (class "Default")
      (node (ref "Q14") (pin "1") (pinfunction "B_1") (pintype "passive"))
      (node (ref "Q15") (pin "1") (pinfunction "B_1") (pintype "passive"))
      (node (ref "R162") (pin "2") (pinfunction "2_2") (pintype "passive"))
      (node (ref "U25") (pin "3") (pinfunction "A_3") (pintype "passive"))
    )
    (net (code "49") (name "Net-(Q14-E)") (class "Default")
      (node (ref "Q14") (pin "2") (pinfunction "E_2") (pintype "passive"))
      (node (ref "R25") (pin "1") (pinfunction "1_1") (pintype "passive"))
    )
    (net (code "50") (name "Net-(Q15-E)") (class "Default")
      (node (ref "Q15") (pin "2") (pinfunction "E_2") (pintype "passive"))
      (node (ref "R124") (pin "1") (pinfunction "1_1") (pintype "passive"))
    )
    (net (code "51") (name "Net-(R128-Pad2)") (class "Default")
      (node (ref "R128") (pin "2") (pinfunction "2_2") (pintype "passive"))
      (node (ref "R129") (pin "1") (pinfunction "1_1") (pintype "passive"))
      (node (ref "R132") (pin "2") (pinfunction "2_2") (pintype "passive"))
    )
    (net (code "52") (name "Net-(U21-Cp_AUX)") (class "Default")
      (node (ref "C25") (pin "2") (pinfunction "2_2") (pintype "passive"))
      (node (ref "C38") (pin "2") (pinfunction "2_2") (pintype "passive"))
      (node (ref "L28") (pin "1") (pinfunction "1_1") (pintype "passive"))
      (node (ref "U21") (pin "7") (pinfunction "Cp_AUX_7") (pintype "passive"))
    )
    (net (code "53") (name "Net-(U21-Cp_MAIN)") (class "Default")
      (node (ref "C242") (pin "2") (pinfunction "2_2") (pintype "passive"))
      (node (ref "C243") (pin "1") (pinfunction "1_1") (pintype "passive"))
      (node (ref "L35") (pin "1") (pinfunction "1_1") (pintype "passive"))
      (node (ref "U21") (pin "10") (pinfunction "Cp_MAIN_10") (pintype "passive"))
    )
    (net (code "54") (name "Net-(U21-EN_AUX)") (class "Default")
      (node (ref "C22") (pin "2") (pinfunction "2_2") (pintype "passive"))
      (node (ref "L15") (pin "1") (pinfunction "1_1") (pintype "passive"))
      (node (ref "U21") (pin "6") (pinfunction "Vcc_AUX_6") (pintype "power_in"))
      (node (ref "U21") (pin "8") (pinfunction "EN_AUX_8") (pintype "input"))
    )
    (net (code "55") (name "Net-(U21-EN_MAIN)") (class "Default")
      (node (ref "C23") (pin "2") (pinfunction "2_2") (pintype "passive"))
      (node (ref "L20") (pin "1") (pinfunction "1_1") (pintype "passive"))
      (node (ref "U21") (pin "11") (pinfunction "Vcc_MAIN_11") (pintype "power_in"))
      (node (ref "U21") (pin "9") (pinfunction "EN_MAIN_9") (pintype "input"))
    )
    (net (code "56") (name "Net-(U21-Fin_AUX)") (class "Default")
      (node (ref "R55") (pin "2") (pinfunction "2_2") (pintype "passive"))
      (node (ref "U21") (pin "5") (pinfunction "Fin_AUX_5") (pintype "passive"))
    )
    (net (code "57") (name "Net-(U21-Fin_MAIN)") (class "Default")
      (node (ref "R56") (pin "1") (pinfunction "1_1") (pintype "passive"))
      (node (ref "U21") (pin "12") (pinfunction "Fin_MAIN_12") (pintype "passive"))
    )
    (net (code "58") (name "Net-(U21-OSC_IN)") (class "Default")
      (node (ref "C150") (pin "1") (pinfunction "1_1") (pintype "passive"))
      (node (ref "U21") (pin "2") (pinfunction "OSC_IN_2") (pintype "input"))
    )
    (net (code "59") (name "Net-(U21-OSC_OUT)") (class "Default")
      (node (ref "C140") (pin "1") (pinfunction "1_1") (pintype "passive"))
      (node (ref "U21") (pin "3") (pinfunction "OSC_OUT_3") (pintype "output"))
    )
    (net (code "60") (name "Net-(U24A-INA+)") (class "Default")
      (node (ref "C231") (pin "1") (pinfunction "1_1") (pintype "passive"))
      (node (ref "R125") (pin "1") (pinfunction "1_1") (pintype "passive"))
      (node (ref "R133") (pin "1") (pinfunction "1_1") (pintype "passive"))
      (node (ref "U24") (pin "3") (pinfunction "INA+_3") (pintype "input"))
    )
    (net (code "61") (name "Net-(U24A-INA-)") (class "Default")
      (node (ref "C154") (pin "2") (pinfunction "2_2") (pintype "passive"))
      (node (ref "R130") (pin "2") (pinfunction "2_2") (pintype "passive"))
      (node (ref "U24") (pin "2") (pinfunction "INA-_2") (pintype "input"))
    )
    (net (code "62") (name "Net-(U24A-OUTA)") (class "Default")
      (node (ref "C154") (pin "1") (pinfunction "1_1") (pintype "passive"))
      (node (ref "R127") (pin "1") (pinfunction "1_1") (pintype "passive"))
      (node (ref "R131") (pin "1") (pinfunction "1_1") (pintype "passive"))
      (node (ref "U24") (pin "1") (pinfunction "OUTA_1") (pintype "output"))
    )
    (net (code "63") (name "Net-(U24B-INB+)") (class "Default")
      (node (ref "C247") (pin "1") (pinfunction "1_1") (pintype "passive"))
      (node (ref "R150") (pin "1") (pinfunction "1_1") (pintype "passive"))
      (node (ref "R151") (pin "1") (pinfunction "1_1") (pintype "passive"))
      (node (ref "U24") (pin "5") (pinfunction "INB+_5") (pintype "input"))
    )
    (net (code "64") (name "Net-(U24B-INB-)") (class "Default")
      (node (ref "C237") (pin "2") (pinfunction "2_2") (pintype "passive"))
      (node (ref "R141") (pin "1") (pinfunction "1_1") (pintype "passive"))
      (node (ref "U24") (pin "6") (pinfunction "INB-_6") (pintype "input"))
    )
    (net (code "65") (name "Net-(U24B-OUTB)") (class "Default")
      (node (ref "C237") (pin "1") (pinfunction "1_1") (pintype "passive"))
      (node (ref "R138") (pin "1") (pinfunction "1_1") (pintype "passive"))
      (node (ref "R33") (pin "1") (pinfunction "1_1") (pintype "passive"))
      (node (ref "U24") (pin "7") (pinfunction "OUTB_7") (pintype "output"))
    )
    (net (code "66") (name "RFIN_GND") (class "Default")
      (node (ref "C139") (pin "2") (pinfunction "2_2") (pintype "passive"))
      (node (ref "C140") (pin "2") (pinfunction "2_2") (pintype "passive"))
      (node (ref "C149") (pin "2") (pinfunction "2_2") (pintype "passive"))
      (node (ref "C19") (pin "1") (pinfunction "1_1") (pintype "passive"))
      (node (ref "C21") (pin "1") (pinfunction "1_1") (pintype "passive"))
      (node (ref "C22") (pin "1") (pinfunction "1_1") (pintype "passive"))
      (node (ref "C240") (pin "2") (pinfunction "2_2") (pintype "passive"))
      (node (ref "C248") (pin "2") (pinfunction "2_2") (pintype "passive"))
      (node (ref "C25") (pin "1") (pinfunction "1_1") (pintype "passive"))
      (node (ref "C27") (pin "1") (pinfunction "1_1") (pintype "passive"))
      (node (ref "C28") (pin "1") (pinfunction "1_1") (pintype "passive"))
      (node (ref "C33") (pin "2") (pinfunction "2_2") (pintype "passive"))
      (node (ref "C79") (pin "2") (pinfunction "2_2") (pintype "passive"))
      (node (ref "D1") (pin "2") (pinfunction "A_2") (pintype "passive"))
      (node (ref "L31") (pin "1") (pinfunction "1_1") (pintype "passive"))
      (node (ref "Q9") (pin "2") (pinfunction "E_2") (pintype "passive"))
      (node (ref "R116") (pin "2") (pinfunction "2_2") (pintype "passive"))
      (node (ref "R117") (pin "2") (pinfunction "2_2") (pintype "passive"))
      (node (ref "R35") (pin "1") (pinfunction "1_1") (pintype "passive"))
      (node (ref "U21") (pin "4") (pinfunction "GND_4") (pintype "power_in"))
    )
  )
)
